# 04-OUTPUT.net
KiCad netlist of a schematic drawn in Altium Designer
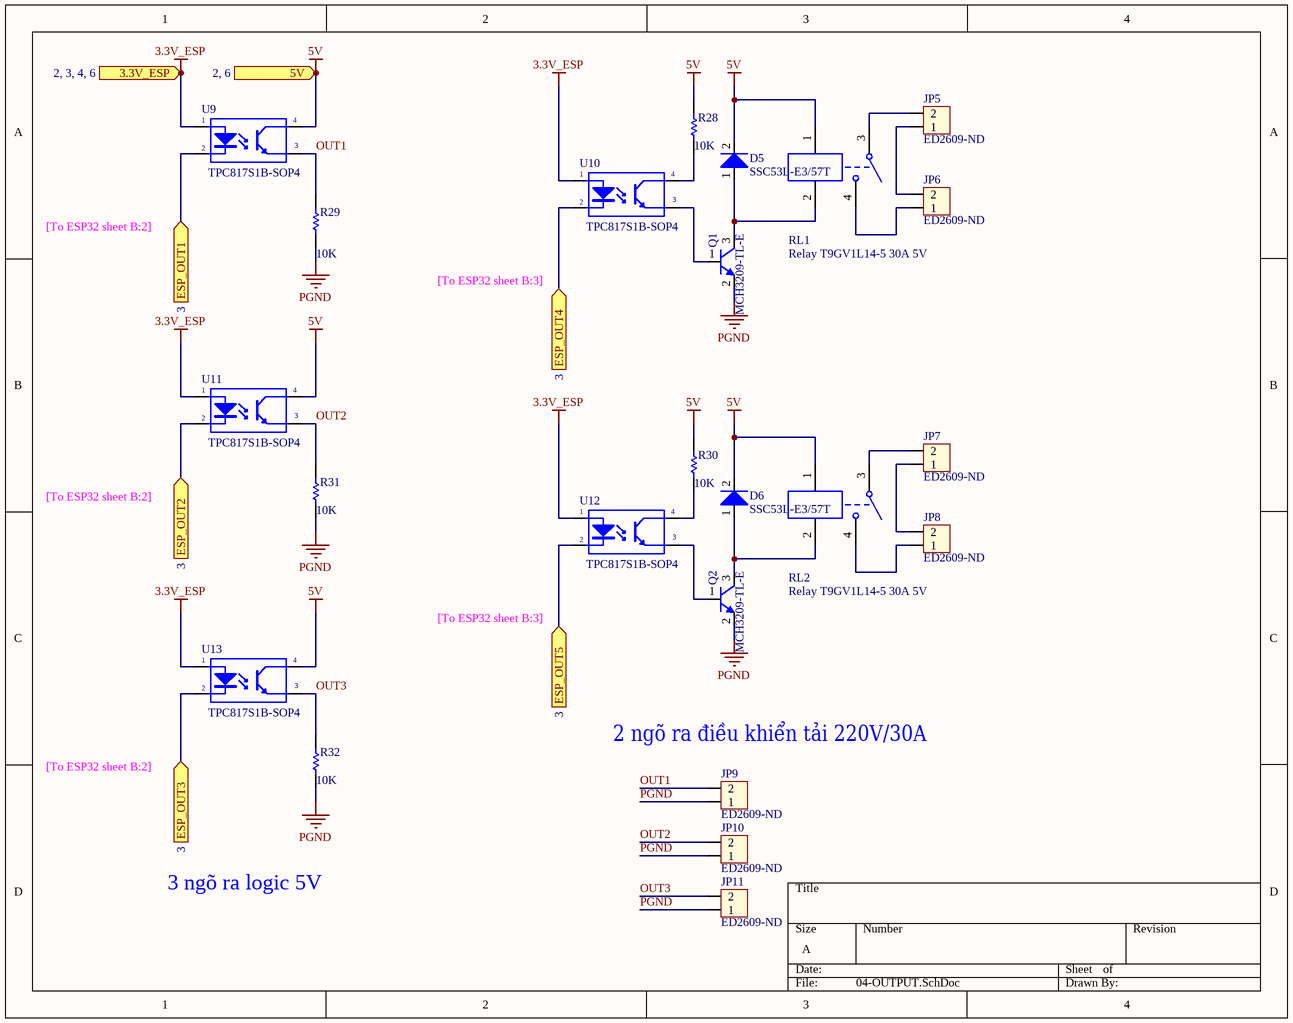
[diagram p0: 04-OUTPUT.SchDoc]

(export (version "E")
  (design (tool "Eeschema 10.0.6"))
  (components
    (comp (ref "D5")
      (value "SSC53L-E3/57T")
      (footprint "SSC53L-E3/57T")
      (description "DIODE SCHOTTKY 30V 5A DO214AB")
      (libsource (lib "lpson") (part "10A10"))
    )
    (comp (ref "D6")
      (value "SSC53L-E3/57T")
      (footprint "SSC53L-E3/57T")
      (description "DIODE SCHOTTKY 30V 5A DO214AB")
      (libsource (lib "lpson") (part "10A10"))
    )
    (comp (ref "JP5")
      (value "ED2609-ND")
      (footprint "DOMINO_OSTTC_2P")
      (description "2 Position Wire to Board Terminal Block Horizontal with Board 0.200\" (5.08mm) Through Hole")
      (libsource (lib "lpson") (part "Con2"))
    )
    (comp (ref "JP6")
      (value "ED2609-ND")
      (footprint "DOMINO_OSTTC_2P")
      (description "2 Position Wire to Board Terminal Block Horizontal with Board 0.200\" (5.08mm) Through Hole")
      (libsource (lib "lpson") (part "Con2"))
    )
    (comp (ref "JP7")
      (value "ED2609-ND")
      (footprint "DOMINO_OSTTC_2P")
      (description "2 Position Wire to Board Terminal Block Horizontal with Board 0.200\" (5.08mm) Through Hole")
      (libsource (lib "lpson") (part "Con2"))
    )
    (comp (ref "JP8")
      (value "ED2609-ND")
      (footprint "DOMINO_OSTTC_2P")
      (description "2 Position Wire to Board Terminal Block Horizontal with Board 0.200\" (5.08mm) Through Hole")
      (libsource (lib "lpson") (part "Con2"))
    )
    (comp (ref "JP9")
      (value "ED2609-ND")
      (footprint "DOMINO_OSTTC_2P")
      (description "2 Position Wire to Board Terminal Block Horizontal with Board 0.200\" (5.08mm) Through Hole")
      (libsource (lib "lpson") (part "Con2"))
    )
    (comp (ref "JP10")
      (value "ED2609-ND")
      (footprint "DOMINO_OSTTC_2P")
      (description "2 Position Wire to Board Terminal Block Horizontal with Board 0.200\" (5.08mm) Through Hole")
      (libsource (lib "lpson") (part "Con2"))
    )
    (comp (ref "JP11")
      (value "ED2609-ND")
      (footprint "DOMINO_OSTTC_2P")
      (description "2 Position Wire to Board Terminal Block Horizontal with Board 0.200\" (5.08mm) Through Hole")
      (libsource (lib "lpson") (part "Con2"))
    )
    (comp (ref "Q1")
      (value "MCH3209-TL-E")
      (footprint "MCH3209-TL-E  SOT-323")
      (description "Bipolar (BJT) Transistor NPN 30V 3A 450MHz 800mW Surface Mount 3-MCPH")
      (libsource (lib "lpson") (part "2SC1815"))
    )
    (comp (ref "Q2")
      (value "MCH3209-TL-E")
      (footprint "MCH3209-TL-E  SOT-323")
      (description "Bipolar (BJT) Transistor NPN 30V 3A 450MHz 800mW Surface Mount 3-MCPH")
      (libsource (lib "lpson") (part "2SC1815"))
    )
    (comp (ref "R28")
      (value "10K")
      (footprint "Res 0805 SMD")
      (description "RES SMD 249K OHM 1% 1/10W 0805")
      (fields
        (field (name "MANUFACTURER") "Yageo")
        (field (name "MANUFACTURER PART NUMBER") "RC0603FR-07249KL")
      )
      (libsource (lib "GSHT_181013") (part "249K/R0805/1%"))
    )
    (comp (ref "R29")
      (value "10K")
      (footprint "Res 0805 SMD")
      (description "RES SMD 249K OHM 1% 1/10W 0805")
      (fields
        (field (name "MANUFACTURER") "Yageo")
        (field (name "MANUFACTURER PART NUMBER") "RC0603FR-07249KL")
      )
      (libsource (lib "GSHT_181013") (part "249K/R0805/1%"))
    )
    (comp (ref "R30")
      (value "10K")
      (footprint "Res 0805 SMD")
      (description "RES SMD 249K OHM 1% 1/10W 0805")
      (fields
        (field (name "MANUFACTURER") "Yageo")
        (field (name "MANUFACTURER PART NUMBER") "RC0603FR-07249KL")
      )
      (libsource (lib "GSHT_181013") (part "249K/R0805/1%"))
    )
    (comp (ref "R31")
      (value "10K")
      (footprint "Res 0805 SMD")
      (description "RES SMD 249K OHM 1% 1/10W 0805")
      (fields
        (field (name "MANUFACTURER") "Yageo")
        (field (name "MANUFACTURER PART NUMBER") "RC0603FR-07249KL")
      )
      (libsource (lib "GSHT_181013") (part "249K/R0805/1%"))
    )
    (comp (ref "R32")
      (value "10K")
      (footprint "Res 0805 SMD")
      (description "RES SMD 249K OHM 1% 1/10W 0805")
      (fields
        (field (name "MANUFACTURER") "Yageo")
        (field (name "MANUFACTURER PART NUMBER") "RC0603FR-07249KL")
      )
      (libsource (lib "GSHT_181013") (part "249K/R0805/1%"))
    )
    (comp (ref "RL1")
      (value "Relay T9GV1L14-5 30A 5V")
      (footprint "Relay T9GV1L14-5 30A 5V")
      (description "General Purpose Relay SPST-NO (1 Form A) 5VDC Coil Through Hole")
      (libsource (lib "PCB_ESP32_RFID") (part "Relay T9GV1L14-5 30A 5V"))
    )
    (comp (ref "RL2")
      (value "Relay T9GV1L14-5 30A 5V")
      (footprint "Relay T9GV1L14-5 30A 5V")
      (description "General Purpose Relay SPST-NO (1 Form A) 5VDC Coil Through Hole")
      (libsource (lib "PCB_ESP32_RFID") (part "Relay T9GV1L14-5 30A 5V"))
    )
    (comp (ref "U9")
      (value "TPC817S1B-SOP4")
      (footprint "TPC817-4SOP")
      (description "Optoisolator Transistor Output 5000Vrms 1 Channel 4-SOP")
      (libsource (lib "lpson") (part "PC817"))
    )
    (comp (ref "U10")
      (value "TPC817S1B-SOP4")
      (footprint "TPC817-4SOP")
      (description "Optoisolator Transistor Output 5000Vrms 1 Channel 4-SOP")
      (libsource (lib "lpson") (part "PC817"))
    )
    (comp (ref "U11")
      (value "TPC817S1B-SOP4")
      (footprint "TPC817-4SOP")
      (description "Optoisolator Transistor Output 5000Vrms 1 Channel 4-SOP")
      (libsource (lib "lpson") (part "PC817"))
    )
    (comp (ref "U12")
      (value "TPC817S1B-SOP4")
      (footprint "TPC817-4SOP")
      (description "Optoisolator Transistor Output 5000Vrms 1 Channel 4-SOP")
      (libsource (lib "lpson") (part "PC817"))
    )
    (comp (ref "U13")
      (value "TPC817S1B-SOP4")
      (footprint "TPC817-4SOP")
      (description "Optoisolator Transistor Output 5000Vrms 1 Channel 4-SOP")
      (libsource (lib "lpson") (part "PC817"))
    )
  )
  (nets
    (net (code "1") (name "/ESP_OUT1") (class "Default")
      (node (ref "U9") (pin "2") (pinfunction "K_2") (pintype "passive"))
    )
    (net (code "2") (name "/ESP_OUT2") (class "Default")
      (node (ref "U11") (pin "2") (pinfunction "K_2") (pintype "passive"))
    )
    (net (code "3") (name "/ESP_OUT3") (class "Default")
      (node (ref "U13") (pin "2") (pinfunction "K_2") (pintype "passive"))
    )
    (net (code "4") (name "/ESP_OUT4") (class "Default")
      (node (ref "U10") (pin "2") (pinfunction "K_2") (pintype "passive"))
    )
    (net (code "5") (name "/ESP_OUT5") (class "Default")
      (node (ref "U12") (pin "2") (pinfunction "K_2") (pintype "passive"))
    )
    (net (code "6") (name "/OUT1") (class "Default")
      (node (ref "JP9") (pin "2") (pinfunction "2_2") (pintype "passive"))
      (node (ref "R29") (pin "2") (pinfunction "2_2") (pintype "passive"))
      (node (ref "U9") (pin "3") (pinfunction "E_3") (pintype "passive"))
    )
    (net (code "7") (name "/OUT2") (class "Default")
      (node (ref "JP10") (pin "2") (pinfunction "2_2") (pintype "passive"))
      (node (ref "R31") (pin "2") (pinfunction "2_2") (pintype "passive"))
      (node (ref "U11") (pin "3") (pinfunction "E_3") (pintype "passive"))
    )
    (net (code "8") (name "/OUT3") (class "Default")
      (node (ref "JP11") (pin "2") (pinfunction "2_2") (pintype "passive"))
      (node (ref "R32") (pin "2") (pinfunction "2_2") (pintype "passive"))
      (node (ref "U13") (pin "3") (pinfunction "E_3") (pintype "passive"))
    )
    (net (code "9") (name "3.3V_ESP") (class "Default")
      (node (ref "U10") (pin "1") (pinfunction "A_1") (pintype "passive"))
      (node (ref "U11") (pin "1") (pinfunction "A_1") (pintype "passive"))
      (node (ref "U12") (pin "1") (pinfunction "A_1") (pintype "passive"))
      (node (ref "U13") (pin "1") (pinfunction "A_1") (pintype "passive"))
      (node (ref "U9") (pin "1") (pinfunction "A_1") (pintype "passive"))
    )
    (net (code "10") (name "5V") (class "Default")
      (node (ref "D5") (pin "2") (pinfunction "K_2") (pintype "passive"))
      (node (ref "D6") (pin "2") (pinfunction "K_2") (pintype "passive"))
      (node (ref "R28") (pin "2") (pinfunction "2_2") (pintype "passive"))
      (node (ref "R30") (pin "2") (pinfunction "2_2") (pintype "passive"))
      (node (ref "RL1") (pin "1") (pinfunction "1_1") (pintype "passive"))
      (node (ref "RL2") (pin "1") (pinfunction "1_1") (pintype "passive"))
      (node (ref "U11") (pin "4") (pinfunction "C_4") (pintype "passive"))
      (node (ref "U13") (pin "4") (pinfunction "C_4") (pintype "passive"))
      (node (ref "U9") (pin "4") (pinfunction "C_4") (pintype "passive"))
    )
    (net (code "11") (name "Net-(D5-A)") (class "Default")
      (node (ref "D5") (pin "1") (pinfunction "A_1") (pintype "passive"))
      (node (ref "Q1") (pin "3") (pinfunction "C_3") (pintype "passive"))
      (node (ref "RL1") (pin "2") (pinfunction "2_2") (pintype "passive"))
    )
    (net (code "12") (name "Net-(D6-A)") (class "Default")
      (node (ref "D6") (pin "1") (pinfunction "A_1") (pintype "passive"))
      (node (ref "Q2") (pin "3") (pinfunction "C_3") (pintype "passive"))
      (node (ref "RL2") (pin "2") (pinfunction "2_2") (pintype "passive"))
    )
    (net (code "13") (name "Net-(JP5-Pad1)") (class "Default")
      (node (ref "JP5") (pin "1") (pinfunction "1_1") (pintype "passive"))
      (node (ref "JP6") (pin "2") (pinfunction "2_2") (pintype "passive"))
    )
    (net (code "14") (name "Net-(JP5-Pad2)") (class "Default")
      (node (ref "JP5") (pin "2") (pinfunction "2_2") (pintype "passive"))
      (node (ref "RL1") (pin "3") (pinfunction "3_3") (pintype "passive"))
    )
    (net (code "15") (name "Net-(JP6-Pad1)") (class "Default")
      (node (ref "JP6") (pin "1") (pinfunction "1_1") (pintype "passive"))
      (node (ref "RL1") (pin "4") (pinfunction "4_4") (pintype "passive"))
    )
    (net (code "16") (name "Net-(JP7-Pad1)") (class "Default")
      (node (ref "JP7") (pin "1") (pinfunction "1_1") (pintype "passive"))
      (node (ref "JP8") (pin "2") (pinfunction "2_2") (pintype "passive"))
    )
    (net (code "17") (name "Net-(JP7-Pad2)") (class "Default")
      (node (ref "JP7") (pin "2") (pinfunction "2_2") (pintype "passive"))
      (node (ref "RL2") (pin "3") (pinfunction "3_3") (pintype "passive"))
    )
    (net (code "18") (name "Net-(JP8-Pad1)") (class "Default")
      (node (ref "JP8") (pin "1") (pinfunction "1_1") (pintype "passive"))
      (node (ref "RL2") (pin "4") (pinfunction "4_4") (pintype "passive"))
    )
    (net (code "19") (name "Net-(Q1-B)") (class "Default")
      (node (ref "Q1") (pin "1") (pinfunction "B_1") (pintype "passive"))
      (node (ref "U10") (pin "3") (pinfunction "E_3") (pintype "passive"))
    )
    (net (code "20") (name "Net-(Q2-B)") (class "Default")
      (node (ref "Q2") (pin "1") (pinfunction "B_1") (pintype "passive"))
      (node (ref "U12") (pin "3") (pinfunction "E_3") (pintype "passive"))
    )
    (net (code "21") (name "Net-(U10-C)") (class "Default")
      (node (ref "R28") (pin "1") (pinfunction "1_1") (pintype "passive"))
      (node (ref "U10") (pin "4") (pinfunction "C_4") (pintype "passive"))
    )
    (net (code "22") (name "Net-(U12-C)") (class "Default")
      (node (ref "R30") (pin "1") (pinfunction "1_1") (pintype "passive"))
      (node (ref "U12") (pin "4") (pinfunction "C_4") (pintype "passive"))
    )
    (net (code "23") (name "PGND") (class "Default")
      (node (ref "JP10") (pin "1") (pinfunction "1_1") (pintype "passive"))
      (node (ref "JP11") (pin "1") (pinfunction "1_1") (pintype "passive"))
      (node (ref "JP9") (pin "1") (pinfunction "1_1") (pintype "passive"))
      (node (ref "Q1") (pin "2") (pinfunction "E_2") (pintype "passive"))
      (node (ref "Q2") (pin "2") (pinfunction "E_2") (pintype "passive"))
      (node (ref "R29") (pin "1") (pinfunction "1_1") (pintype "passive"))
      (node (ref "R31") (pin "1") (pinfunction "1_1") (pintype "passive"))
      (node (ref "R32") (pin "1") (pinfunction "1_1") (pintype "passive"))
    )
  )
)
